# TSL25911-Breakout_v11.net
KiCad netlist of a schematic drawn in EAGLE
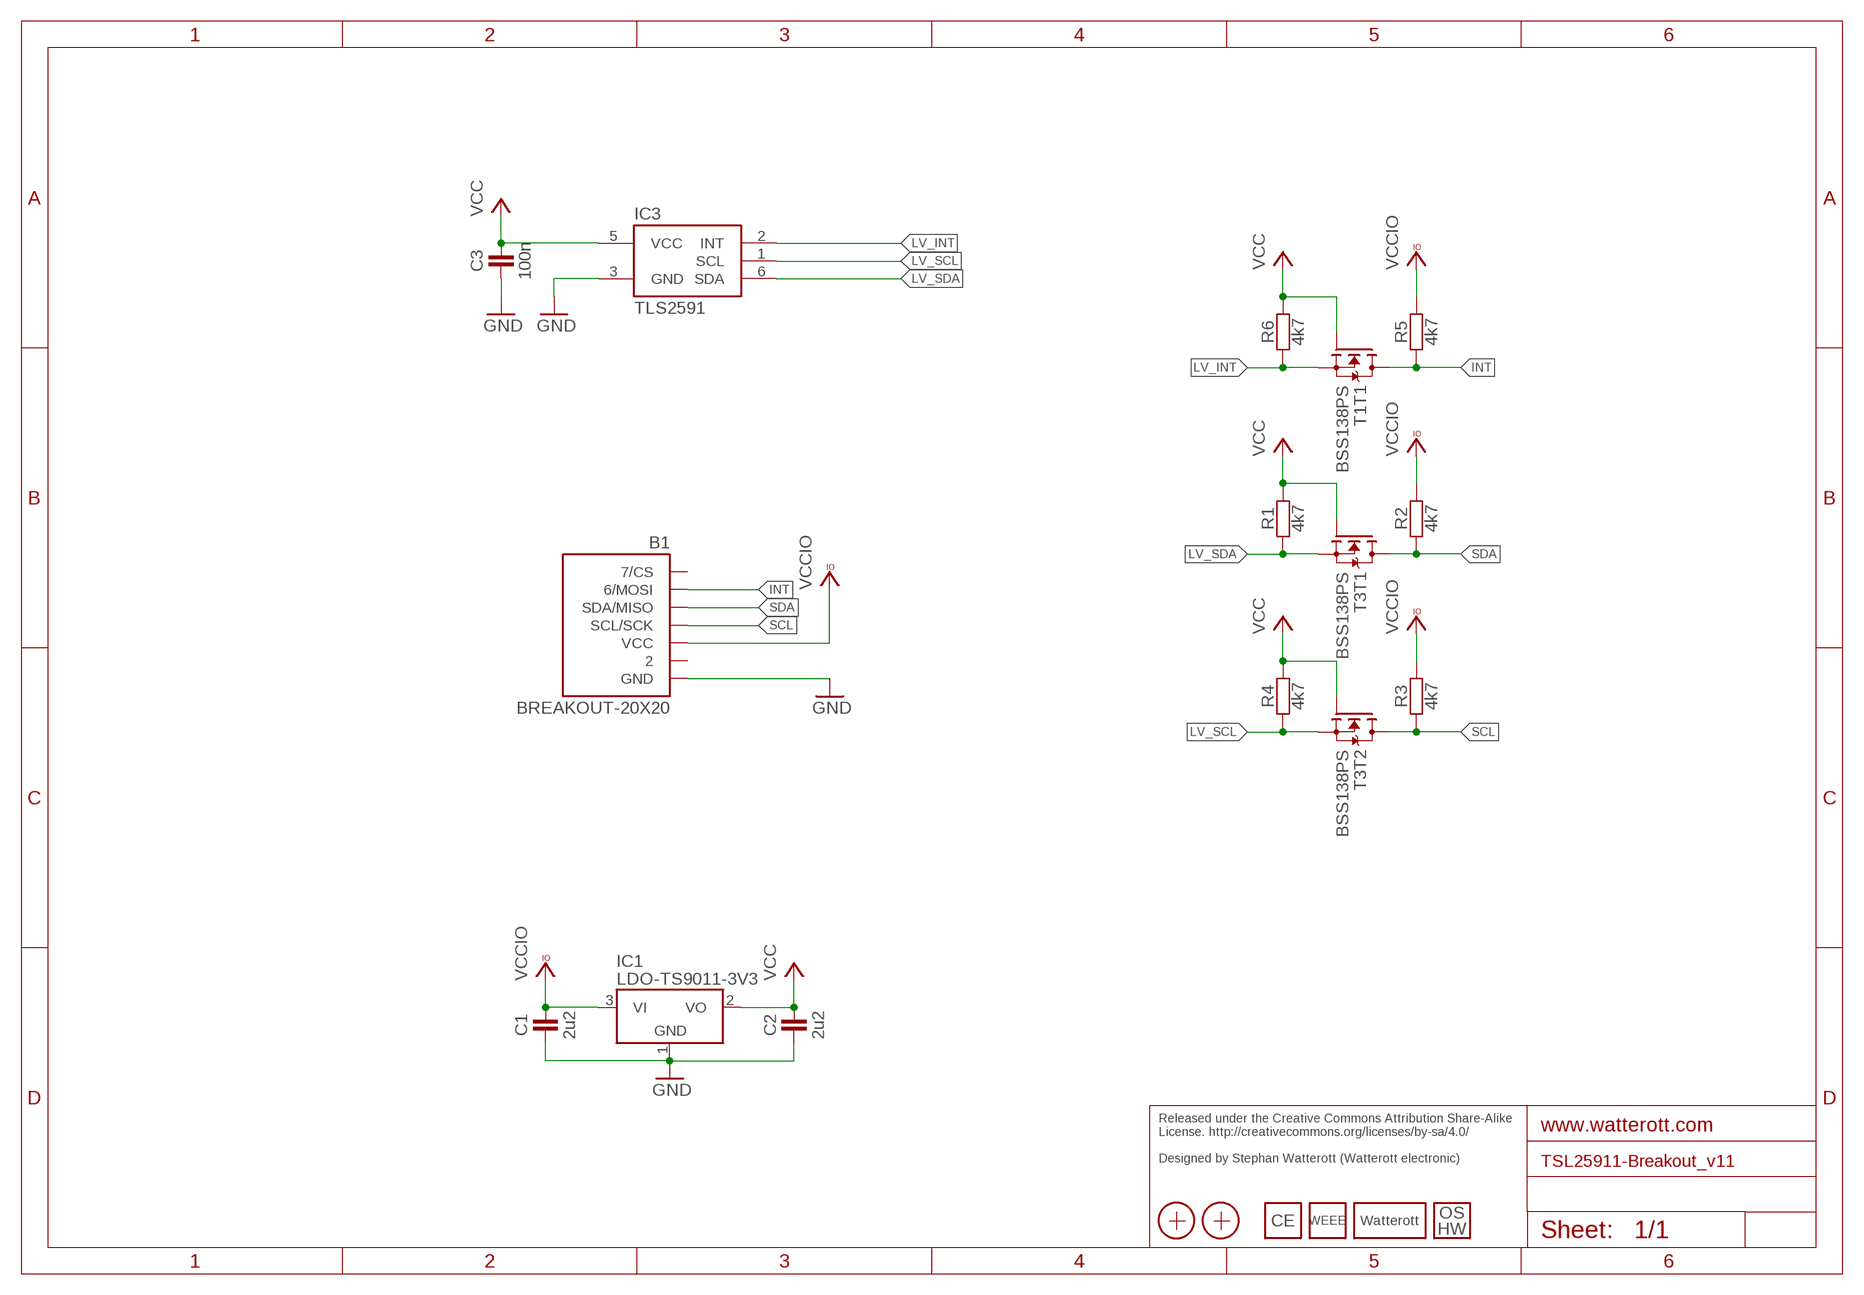
[diagram p0: schematic, sheet 1]

(export (version "E")
  (design (tool "Eeschema 10.0.6"))
  (components
    (comp (ref "B1")
      (value "BREAKOUT-20X20")
      (footprint "eagle-import:BREAKOUT-20X20")
      (libsource (lib "eagle-import") (part "BREAKOUT-20X20"))
    )
    (comp (ref "C1")
      (value "2u2")
      (footprint "eagle-import:C0402")
      (libsource (lib "eagle-import") (part "CAPACITOR-0402"))
    )
    (comp (ref "C2")
      (value "2u2")
      (footprint "eagle-import:C0402")
      (libsource (lib "eagle-import") (part "CAPACITOR-0402"))
    )
    (comp (ref "C3")
      (value "100n")
      (footprint "eagle-import:C0402")
      (libsource (lib "eagle-import") (part "CAPACITOR-0402"))
    )
    (comp (ref "IC1")
      (value "LDO-TS9011-3V3")
      (footprint "eagle-import:SOT23")
      (libsource (lib "eagle-import") (part "LDO-TS9011-3V3"))
    )
    (comp (ref "IC3")
      (value "TLS2591")
      (footprint "eagle-import:WFDFN6")
      (libsource (lib "eagle-import") (part "TLS2591"))
    )
    (comp (ref "LOGO3")
      (value "LOGO_WEEE-4")
      (footprint "eagle-import:WEEE_4MM")
      (libsource (lib "eagle-import") (part "LOGO_WEEE-4"))
    )
    (comp (ref "LOGO4")
      (value "LOGO_CE-4")
      (footprint "eagle-import:CE_4MM")
      (libsource (lib "eagle-import") (part "LOGO_CE-4"))
    )
    (comp (ref "LOGO5")
      (value "LOGO_SPARK-4")
      (footprint "eagle-import:SPARK_4MM")
      (libsource (lib "eagle-import") (part "LOGO_SPARK-4"))
    )
    (comp (ref "LOGO6")
      (value "LOGO_OSHW-2")
      (footprint "eagle-import:OSHW_2MM")
      (libsource (lib "eagle-import") (part "LOGO_OSHW-2"))
    )
    (comp (ref "R1")
      (value "4k7")
      (footprint "eagle-import:C0402")
      (libsource (lib "eagle-import") (part "RESISTOR-0402"))
    )
    (comp (ref "R2")
      (value "4k7")
      (footprint "eagle-import:C0402")
      (libsource (lib "eagle-import") (part "RESISTOR-0402"))
    )
    (comp (ref "R3")
      (value "4k7")
      (footprint "eagle-import:C0402")
      (libsource (lib "eagle-import") (part "RESISTOR-0402"))
    )
    (comp (ref "R4")
      (value "4k7")
      (footprint "eagle-import:C0402")
      (libsource (lib "eagle-import") (part "RESISTOR-0402"))
    )
    (comp (ref "R5")
      (value "4k7")
      (footprint "eagle-import:C0402")
      (libsource (lib "eagle-import") (part "RESISTOR-0402"))
    )
    (comp (ref "R6")
      (value "4k7")
      (footprint "eagle-import:C0402")
      (libsource (lib "eagle-import") (part "RESISTOR-0402"))
    )
    (comp (ref "T1")
      (value "BSS138PS")
      (footprint "eagle-import:SOT363")
      (libsource (lib "eagle-import") (part "BSS138PS"))
    )
    (comp (ref "T3")
      (value "BSS138PS")
      (footprint "eagle-import:SOT363")
      (libsource (lib "eagle-import") (part "BSS138PS"))
    )
    (comp (ref "X1")
      (value "PASSER-07")
      (footprint "eagle-import:PASSER_07MM")
      (libsource (lib "eagle-import") (part "PASSER-07"))
    )
    (comp (ref "X2")
      (value "PASSER-07")
      (footprint "eagle-import:PASSER_07MM")
      (libsource (lib "eagle-import") (part "PASSER-07"))
    )
  )
  (nets
    (net (code "1") (name "GND") (class "Default")
      (node (ref "B1") (pin "GND") (pinfunction "GND_GND") (pintype "power_in"))
      (node (ref "C1") (pin "1") (pinfunction "1_1") (pintype "passive"))
      (node (ref "C2") (pin "1") (pinfunction "1_1") (pintype "passive"))
      (node (ref "C3") (pin "1") (pinfunction "1_1") (pintype "passive"))
      (node (ref "IC1") (pin "1") (pinfunction "GND_1") (pintype "passive"))
      (node (ref "IC3") (pin "3") (pinfunction "GND_3") (pintype "power_in"))
    )
    (net (code "2") (name "INT") (class "Default")
      (node (ref "B1") (pin "MOSI") (pinfunction "6/MOSI_MOSI") (pintype "bidirectional"))
      (node (ref "R5") (pin "1") (pinfunction "1_1") (pintype "passive"))
      (node (ref "T1") (pin "6") (pinfunction "D_6") (pintype "passive"))
    )
    (net (code "3") (name "LV_INT") (class "Default")
      (node (ref "IC3") (pin "2") (pinfunction "INT_2") (pintype "open_collector"))
      (node (ref "R6") (pin "1") (pinfunction "1_1") (pintype "passive"))
      (node (ref "T1") (pin "1") (pinfunction "S_1") (pintype "passive"))
    )
    (net (code "4") (name "LV_SCL") (class "Default")
      (node (ref "IC3") (pin "1") (pinfunction "SCL_1") (pintype "bidirectional"))
      (node (ref "R4") (pin "1") (pinfunction "1_1") (pintype "passive"))
      (node (ref "T3") (pin "4") (pinfunction "S_4") (pintype "passive"))
    )
    (net (code "5") (name "LV_SDA") (class "Default")
      (node (ref "IC3") (pin "6") (pinfunction "SDA_6") (pintype "bidirectional"))
      (node (ref "R1") (pin "1") (pinfunction "1_1") (pintype "passive"))
      (node (ref "T3") (pin "1") (pinfunction "S_1") (pintype "passive"))
    )
    (net (code "6") (name "SCL") (class "Default")
      (node (ref "B1") (pin "SCL/SCK") (pinfunction "SCL/SCK_SCL/SCK") (pintype "bidirectional"))
      (node (ref "R3") (pin "1") (pinfunction "1_1") (pintype "passive"))
      (node (ref "T3") (pin "3") (pinfunction "D_3") (pintype "passive"))
    )
    (net (code "7") (name "SDA") (class "Default")
      (node (ref "B1") (pin "SDA/MISO") (pinfunction "SDA/MISO_SDA/MISO") (pintype "bidirectional"))
      (node (ref "R2") (pin "1") (pinfunction "1_1") (pintype "passive"))
      (node (ref "T3") (pin "6") (pinfunction "D_6") (pintype "passive"))
    )
    (net (code "8") (name "VCC") (class "Default")
      (node (ref "C2") (pin "2") (pinfunction "2_2") (pintype "passive"))
      (node (ref "C3") (pin "2") (pinfunction "2_2") (pintype "passive"))
      (node (ref "IC1") (pin "2") (pinfunction "VO_2") (pintype "passive"))
      (node (ref "IC3") (pin "5") (pinfunction "VCC_5") (pintype "power_in"))
      (node (ref "R1") (pin "2") (pinfunction "2_2") (pintype "passive"))
      (node (ref "R4") (pin "2") (pinfunction "2_2") (pintype "passive"))
      (node (ref "R6") (pin "2") (pinfunction "2_2") (pintype "passive"))
      (node (ref "T1") (pin "2") (pinfunction "G_2") (pintype "passive"))
      (node (ref "T3") (pin "2") (pinfunction "G_2") (pintype "passive"))
      (node (ref "T3") (pin "5") (pinfunction "G_5") (pintype "passive"))
    )
    (net (code "9") (name "VCCIO") (class "Default")
      (node (ref "B1") (pin "VCC") (pinfunction "VCC_VCC") (pintype "power_in"))
      (node (ref "C1") (pin "2") (pinfunction "2_2") (pintype "passive"))
      (node (ref "IC1") (pin "3") (pinfunction "VI_3") (pintype "input"))
      (node (ref "R2") (pin "2") (pinfunction "2_2") (pintype "passive"))
      (node (ref "R3") (pin "2") (pinfunction "2_2") (pintype "passive"))
      (node (ref "R5") (pin "2") (pinfunction "2_2") (pintype "passive"))
    )
    (net (code "10") (name "unconnected-(B1-7{slash}CS-PadCS)") (class "Default")
      (node (ref "B1") (pin "CS") (pinfunction "7/CS_CS") (pintype "bidirectional"))
    )
    (net (code "11") (name "unconnected-(B1-Pad2)") (class "Default")
      (node (ref "B1") (pin "2") (pinfunction "2_2") (pintype "bidirectional"))
    )
  )
)
